# Top.net
KiCad netlist of a schematic drawn in Altium Designer
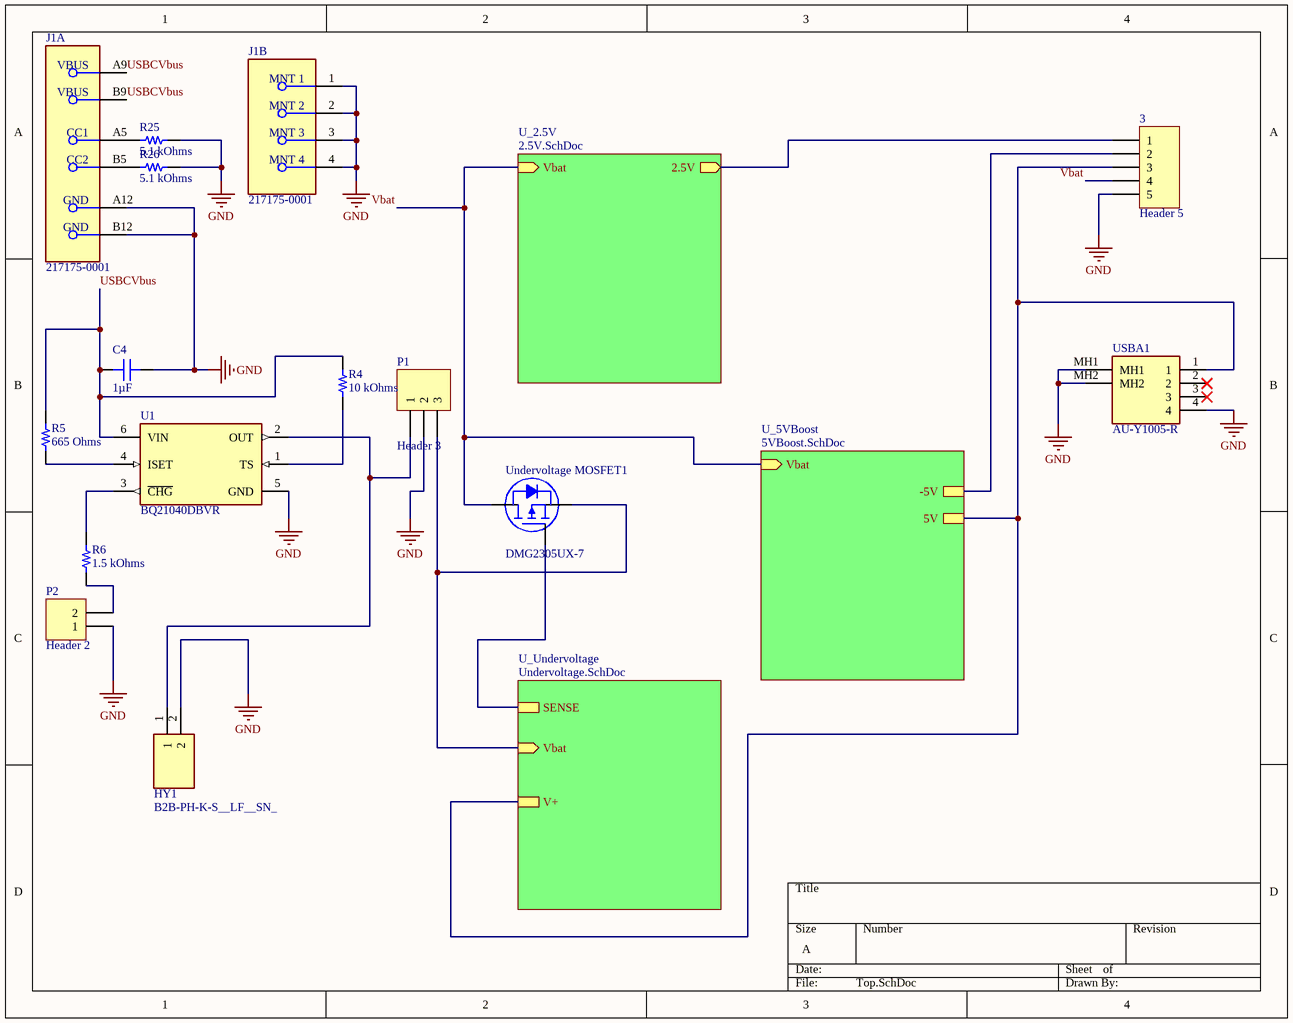
[diagram p0: Top.SchDoc]

(export (version "E")
  (design (tool "Eeschema 10.0.6"))
  (components
    (comp (ref "3")
      (value "Header 5")
      (footprint "HDR1X5")
      (description "Header, 5-Pin")
      (fields (field (name "PUBLISHER") "Altium Limited"))
      (libsource (lib "") (part "Symbol_1"))
    )
    (comp (ref "C4")
      (value "1µF")
      (footprint "CAP 0603_1608")
      (description "CAP CER 1UF 16V X7R 0603")
      (fields (field (name "TOLERANCE") "±20%") (field (name "PART NUMBER") "0603YC105MAT2A"))
      (libsource (lib "Gopher Motorsports") (part "CAPACITOR"))
    )
    (comp (ref "HY1")
      (value "B2B-PH-K-S__LF__SN_")
      (footprint "SamacSys:B2BPHKSLFSN")
      (description "Circulator or Directional Coupler")
      (fields (field (name "MANUFACTURER_PART_NUMBER") "B2B-PH-K-S (LF)(SN)"))
      (libsource (lib "*") (part "B2B-PH-K-S__LF__SN_"))
    )
    (comp (ref "J1")
      (value "217175-0001")
      (footprint "FP-217175-0001-MFG")
      (description "CONN RCP USB2.0 C 6+18P SMD RA")
      (libsource (lib "Altium Content Vault") (part "6a66c69350f09309f94811689c98437"))
    )
    (comp (ref "P1")
      (value "Header 3")
      (footprint "HDR1X3")
      (description "Header, 3-Pin")
      (fields (field (name "PUBLISHER") "Altium Limited"))
      (libsource (lib "Gopher Motorsports") (part "Symbol"))
    )
    (comp (ref "P2")
      (value "Header 2")
      (footprint "HDR1X2")
      (description "Header, 2-Pin")
      (fields (field (name "PUBLISHER") "Altium Limited"))
      (libsource (lib "") (part "Symbol_2"))
    )
    (comp (ref "R4")
      (value "10 kOhms")
      (footprint "RES 0603_1608")
      (description "RES SMD 10K OHM 0.5% 1/16W 0603")
      (fields (field (name "MANUFACTURER") "Susumu") (field (name "PART NUMBER") "RR0816P-103-D"))
      (libsource (lib "Gopher Motorsports") (part "RESISTOR"))
    )
    (comp (ref "R5")
      (value "665 Ohms")
      (footprint "RES 0603_1608")
      (description "RES 665 OHM 1% 1/8W 0603")
      (fields
        (field (name "MANUFACTURER") "KOA Speer Electronics, Inc.")
        (field (name "PART NUMBER") "RK73H1JTTD6650F")
      )
      (libsource (lib "Gopher Motorsports") (part "RESISTOR"))
    )
    (comp (ref "R6")
      (value "1.5 kOhms")
      (footprint "RES 0603_1608")
      (description "RES SMD 1.5K OHM 0.1% 1/10W 0603")
      (fields (field (name "TOLERANCE") "±0.1%") (field (name "PART NUMBER") "ERA-3AEB152V"))
      (libsource (lib "Gopher Motorsports") (part "RESISTOR"))
    )
    (comp (ref "R25")
      (value "5.1 kOhms")
      (footprint "RES 0603_1608")
      (description "RES SMD 5.1K OHM 5% 1/10W 0603")
      (fields (field (name "PART NUMBER") "AC0603JR-075K1L") (field (name "MANUFACTURER") "Yageo"))
      (libsource (lib "Gopher Motorsports") (part "RESISTOR"))
    )
    (comp (ref "R26")
      (value "5.1 kOhms")
      (footprint "RES 0603_1608")
      (description "RES SMD 5.1K OHM 5% 1/10W 0603")
      (fields (field (name "PART NUMBER") "AC0603JR-075K1L") (field (name "MANUFACTURER") "Yageo"))
      (libsource (lib "Gopher Motorsports") (part "RESISTOR"))
    )
    (comp (ref "U1")
      (value "BQ21040DBVR")
      (footprint "FP-DBV0006A-MFG")
      (description "IC BATT CHG LI-ION 1CELL SOT23-6")
      (libsource (lib "Altium Content Vault") (part "3ee7d1eb50ab2d5c398f7a34a251785"))
    )
    (comp (ref "Undervoltage MOSFET1")
      (value "DMG2305UX-7")
      (footprint "DIODES SOT-23-3")
      (description "MOSFET P-CH 20V 4.2A SOT23")
      (fields (field (name "MANUFACTURER") "Diodes Incorporated"))
      (libsource (lib "Gopher Motorsports") (part "DIODES MOSFET P-CH SOT-23-3"))
    )
    (comp (ref "USBA1")
      (value "AU-Y1005-R")
      (footprint "SamacSys:AUY1005R")
      (description "Connector")
      (libsource (lib "*") (part "AU-Y1005-R"))
    )
  )
  (nets
    (net (code "1") (name "/-5V") (class "Default")
      (node (ref "3") (pin "2") (pinfunction "2_2") (pintype "passive"))
    )
    (net (code "2") (name "/2.5V") (class "Default")
      (node (ref "3") (pin "1") (pinfunction "1_1") (pintype "passive"))
    )
    (net (code "3") (name "/5V") (class "Default")
      (node (ref "3") (pin "3") (pinfunction "3_3") (pintype "passive"))
      (node (ref "USBA1") (pin "1") (pinfunction "1_1") (pintype "passive"))
    )
    (net (code "4") (name "/SENSE") (class "Default")
      (node (ref "Undervoltage MOSFET1") (pin "1") (pinfunction "G_1") (pintype "passive"))
    )
    (net (code "5") (name "/USBCVbus") (class "Default")
      (node (ref "C4") (pin "1") (pinfunction "1_1") (pintype "passive"))
      (node (ref "J1") (pin "A9") (pinfunction "VBUS_A9") (pintype "power_in"))
      (node (ref "J1") (pin "B9") (pinfunction "VBUS_B9") (pintype "power_in"))
      (node (ref "R4") (pin "1") (pinfunction "1_1") (pintype "passive"))
      (node (ref "R5") (pin "2") (pinfunction "2_2") (pintype "passive"))
      (node (ref "U1") (pin "6") (pinfunction "VIN_6") (pintype "power_in"))
    )
    (net (code "6") (name "/Vbat") (class "Default")
      (node (ref "3") (pin "4") (pinfunction "4_4") (pintype "passive"))
      (node (ref "Undervoltage MOSFET1") (pin "3") (pinfunction "D_3") (pintype "passive"))
    )
    (net (code "7") (name "/Vbat_1") (class "Default")
      (node (ref "P1") (pin "3") (pinfunction "3_3") (pintype "passive"))
      (node (ref "Undervoltage MOSFET1") (pin "2") (pinfunction "S_2") (pintype "passive"))
    )
    (net (code "8") (name "GND") (class "Default")
      (node (ref "3") (pin "5") (pinfunction "5_5") (pintype "passive"))
      (node (ref "C4") (pin "2") (pinfunction "2_2") (pintype "passive"))
      (node (ref "HY1") (pin "2") (pinfunction "2_2") (pintype "passive"))
      (node (ref "J1") (pin "1") (pinfunction "MNT_1_1") (pintype "passive"))
      (node (ref "J1") (pin "2") (pinfunction "MNT_2_2") (pintype "passive"))
      (node (ref "J1") (pin "3") (pinfunction "MNT_3_3") (pintype "passive"))
      (node (ref "J1") (pin "4") (pinfunction "MNT_4_4") (pintype "passive"))
      (node (ref "J1") (pin "A12") (pinfunction "GND_A12") (pintype "power_in"))
      (node (ref "J1") (pin "B12") (pinfunction "GND_B12") (pintype "power_in"))
      (node (ref "P1") (pin "2") (pinfunction "2_2") (pintype "passive"))
      (node (ref "P2") (pin "1") (pinfunction "1_1") (pintype "passive"))
      (node (ref "R25") (pin "2") (pinfunction "2_2") (pintype "passive"))
      (node (ref "R26") (pin "2") (pinfunction "2_2") (pintype "passive"))
      (node (ref "U1") (pin "5") (pinfunction "GND_5") (pintype "power_in"))
      (node (ref "USBA1") (pin "4") (pinfunction "4_4") (pintype "passive"))
      (node (ref "USBA1") (pin "MH1") (pinfunction "MH1_MH1") (pintype "passive"))
      (node (ref "USBA1") (pin "MH2") (pinfunction "MH2_MH2") (pintype "passive"))
    )
    (net (code "9") (name "Net-(J1A-CC1)") (class "Default")
      (node (ref "J1") (pin "A5") (pinfunction "CC1_A5") (pintype "passive"))
      (node (ref "R25") (pin "1") (pinfunction "1_1") (pintype "passive"))
    )
    (net (code "10") (name "Net-(J1A-CC2)") (class "Default")
      (node (ref "J1") (pin "B5") (pinfunction "CC2_B5") (pintype "passive"))
      (node (ref "R26") (pin "1") (pinfunction "1_1") (pintype "passive"))
    )
    (net (code "11") (name "Net-(P2-Pad2)") (class "Default")
      (node (ref "P2") (pin "2") (pinfunction "2_2") (pintype "passive"))
      (node (ref "R6") (pin "1") (pinfunction "1_1") (pintype "passive"))
    )
    (net (code "12") (name "Net-(U1-ISET)") (class "Default")
      (node (ref "R5") (pin "1") (pinfunction "1_1") (pintype "passive"))
      (node (ref "U1") (pin "4") (pinfunction "ISET_4") (pintype "input"))
    )
    (net (code "13") (name "Net-(U1-OUT)") (class "Default")
      (node (ref "HY1") (pin "1") (pinfunction "1_1") (pintype "passive"))
      (node (ref "P1") (pin "1") (pinfunction "1_1") (pintype "passive"))
      (node (ref "U1") (pin "2") (pinfunction "OUT_2") (pintype "output"))
    )
    (net (code "14") (name "Net-(U1-TS)") (class "Default")
      (node (ref "R4") (pin "2") (pinfunction "2_2") (pintype "passive"))
      (node (ref "U1") (pin "1") (pinfunction "TS_1") (pintype "input"))
    )
    (net (code "15") (name "Net-(U1-~{CHG})") (class "Default")
      (node (ref "R6") (pin "2") (pinfunction "2_2") (pintype "passive"))
      (node (ref "U1") (pin "3") (pinfunction "~{CHG}_3") (pintype "output"))
    )
    (net (code "16") (name "unconnected-(USBA1-Pad2)") (class "Default")
      (node (ref "USBA1") (pin "2") (pinfunction "2_2") (pintype "passive+no_connect"))
    )
    (net (code "17") (name "unconnected-(USBA1-Pad3)") (class "Default")
      (node (ref "USBA1") (pin "3") (pinfunction "3_3") (pintype "passive+no_connect"))
    )
  )
)
